# Top_Design.net
KiCad netlist of a schematic drawn in Altium Designer
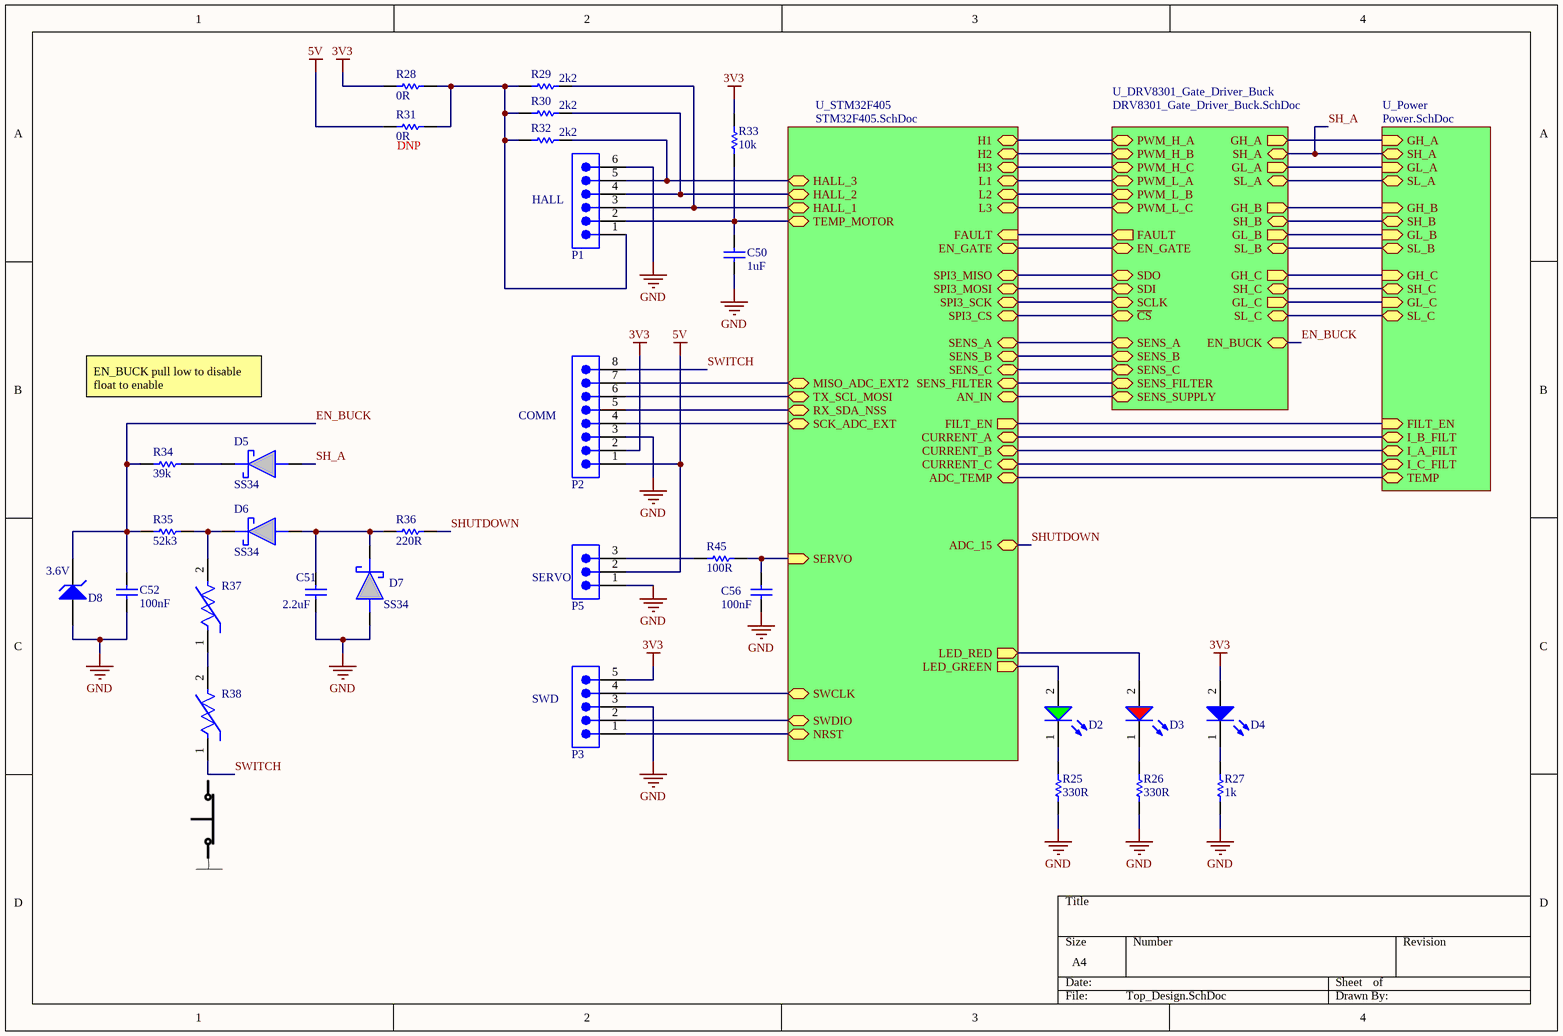
[diagram p0: Top_Design.SchDoc]

(export (version "E")
  (design (tool "Eeschema 10.0.6"))
  (components
    (comp (ref "C50")
      (value "1uF")
      (footprint "Wurth 0603 capacitor")
      (fields (field (name "Comment") "Generic Capacitor 1uF 0603"))
      (libsource (lib "Passives") (part "Generic Capacitor 1uF 0603"))
    )
    (comp (ref "C51")
      (value "2.2uF")
      (footprint "Wurth 0603 capacitor")
      (fields (field (name "Comment") "Generic Capacitor 2.2uF 0603"))
      (libsource (lib "Passives") (part "Generic Capacitor 2.2uF 0603"))
    )
    (comp (ref "C52")
      (value "100nF")
      (footprint "Wurth 0603 capacitor")
      (fields (field (name "Comment") "Generic Capacitor 100nF 0603"))
      (libsource (lib "Passives") (part "Generic Capacitor 100nF 0603"))
    )
    (comp (ref "C56")
      (value "100nF")
      (footprint "Wurth 0603 capacitor")
      (fields (field (name "Comment") "Generic Capacitor 100nF 0603"))
      (libsource (lib "Passives") (part "Generic Capacitor 100nF 0603"))
    )
    (comp (ref "D2")
      (value "Green, 3.2V, 140°")
      (footprint "Wurth 0603 LED")
      (description "WL-SMCD Mono-color Chip LED Diffused, SMT, size 0603, Green, 3.2V, 140°")
      (fields
        (field (name "MANUFACTURER PART NUMBER") "150060GS55040")
        (field (name "MANUFACTURER") "Wurth Elektronik")
      )
      (libsource (lib "LED") (part "LED GREEN 0603"))
    )
    (comp (ref "D3")
      (value "Red, 2V, 140°")
      (footprint "Wurth 0603 LED")
      (description "WL-SMCD Mono-color Chip LED Diffused, SMT, size 0603, Red, 2V, 140°")
      (fields
        (field (name "MANUFACTURER PART NUMBER") "150060RS55040")
        (field (name "MANUFACTURER") "Wurth Elektronik")
      )
      (libsource (lib "LED") (part "LED RED 0603"))
    )
    (comp (ref "D4")
      (value "Blue, 3.2V, 140°")
      (footprint "Wurth 0603 LED")
      (description "WL-SMCD Mono-color Chip LED Diffused, SMT, size 0603, Blue, 3.2V, 140°")
      (fields
        (field (name "MANUFACTURER PART NUMBER") "150060BS55040")
        (field (name "MANUFACTURER") "Wurth Elektronik")
      )
      (libsource (lib "LED") (part "LED BLUE 0603"))
    )
    (comp (ref "D5")
      (value "SS34")
      (footprint "MDD DO-214AC diode")
      (description "SS34 Schottky Barrier Diodes (SBD) SMA(DO-214AC) RoHS")
      (libsource (lib "Passives") (part "MDD SS34"))
    )
    (comp (ref "D6")
      (value "SS34")
      (footprint "MDD DO-214AC diode")
      (description "SS34 Schottky Barrier Diodes (SBD) SMA(DO-214AC) RoHS")
      (libsource (lib "Passives") (part "MDD SS34"))
    )
    (comp (ref "D7")
      (value "SS34")
      (footprint "MDD DO-214AC diode")
      (description "SS34 Schottky Barrier Diodes (SBD) SMA(DO-214AC) RoHS")
      (libsource (lib "Passives") (part "MDD SS34"))
    )
    (comp (ref "D8")
      (value "ROHM EDZVT2R3.6B")
      (footprint "ROHM SOD-523 zener")
      (description "Independent 3.6V~3.845V 150mW 3.6V SOD-523 Zener Diodes ROHS")
      (libsource (lib "Passives") (part "3.6V 150mW zener"))
    )
    (comp (ref "P1")
      (value "61300611121")
      (footprint "6x1 2.54mm M")
      (description "WR-PHD Pin Header, THT, Vertical, pitch 2.54mm, 1 Row, 6P")
      (fields (field (name "MANUFACTURER") "Wurth Elektronik"))
      (libsource (lib "2.54mm_pin_headers") (part "6P"))
    )
    (comp (ref "P2")
      (value "61300811121")
      (footprint "8x1 2.54mm M")
      (description "WR-PHD Pin Header, THT, Vertical, pitch 2.54mm, 1 Row, 8P")
      (fields (field (name "MANUFACTURER") "Wurth Elektronik"))
      (libsource (lib "2.54mm_pin_headers") (part "8P"))
    )
    (comp (ref "P3")
      (value "61300511121")
      (footprint "5x1 2.54mm M")
      (description "WR-PHD Pin Header, THT, Vertical, pitch 2.54mm, 1 Row, 5P")
      (fields (field (name "MANUFACTURER") "Wurth Elektronik"))
      (libsource (lib "2.54mm_pin_headers") (part "5P"))
    )
    (comp (ref "P5")
      (value "61300311121")
      (footprint "3x1 2.54mm M")
      (description "WR-PHD Pin Header, THT, Vertical, pitch 2.54mm, 1 Row, 3P")
      (fields (field (name "MANUFACTURER") "Wurth Elektronik"))
      (libsource (lib "2.54mm_pin_headers") (part "3P"))
    )
    (comp (ref "R25")
      (value "330R")
      (footprint "Wurth 0603 Resistor")
      (fields (field (name "Comment") "Generic Resistor 330R 0603"))
      (libsource (lib "Passives") (part "Generic Resistor 330R 0603"))
    )
    (comp (ref "R26")
      (value "330R")
      (footprint "Wurth 0603 Resistor")
      (fields (field (name "Comment") "Generic Resistor 330R 0603"))
      (libsource (lib "Passives") (part "Generic Resistor 330R 0603"))
    )
    (comp (ref "R27")
      (value "1k")
      (footprint "Wurth 0603 Resistor")
      (fields (field (name "Comment") "Generic Resistor 1k 0603"))
      (libsource (lib "Passives") (part "Generic Resistor 1k 0603"))
    )
    (comp (ref "R28")
      (value "0R")
      (footprint "Wurth 0603 Resistor")
      (fields (field (name "Comment") "Generic Resistor 0R 0603"))
      (libsource (lib "Passives") (part "Generic Resistor 0R 0603"))
    )
    (comp (ref "R29")
      (value "2k2")
      (footprint "Wurth 0603 Resistor")
      (fields (field (name "Comment") "Generic Resistor 2k2 0603"))
      (libsource (lib "Passives") (part "Generic Resistor 2k2 0603"))
    )
    (comp (ref "R30")
      (value "2k2")
      (footprint "Wurth 0603 Resistor")
      (fields (field (name "Comment") "Generic Resistor 2k2 0603"))
      (libsource (lib "Passives") (part "Generic Resistor 2k2 0603"))
    )
    (comp (ref "R31")
      (value "0R")
      (footprint "Wurth 0603 Resistor")
      (fields (field (name "Comment") "Generic Resistor 0R 0603"))
      (libsource (lib "Passives") (part "Generic Resistor 0R 0603"))
    )
    (comp (ref "R32")
      (value "2k2")
      (footprint "Wurth 0603 Resistor")
      (fields (field (name "Comment") "Generic Resistor 2k2 0603"))
      (libsource (lib "Passives") (part "Generic Resistor 2k2 0603"))
    )
    (comp (ref "R33")
      (value "10k")
      (footprint "Wurth 0603 Resistor")
      (fields (field (name "Comment") "Generic Resistor 10k 0603"))
      (libsource (lib "Passives") (part "Generic Resistor 10k 0603"))
    )
    (comp (ref "R34")
      (value "39k")
      (footprint "Wurth 0603 Resistor")
      (fields (field (name "Comment") "Generic Resistor 39k 0603"))
      (libsource (lib "Passives") (part "Generic Resistor 39k 0603"))
    )
    (comp (ref "R35")
      (value "52k3")
      (footprint "Wurth 0603 Resistor")
      (fields (field (name "Comment") "Generic Resistor 52k3 0603"))
      (libsource (lib "Passives") (part "Generic Resistor 52k3 0603"))
    )
    (comp (ref "R36")
      (value "220R")
      (footprint "Wurth 0603 Resistor")
      (fields (field (name "Comment") "Generic Resistor 220R 0603"))
      (libsource (lib "Passives") (part "Generic Resistor 220R 0603"))
    )
    (comp (ref "R37")
      (value "PRF15BC102RB6RC")
      (footprint "FP-PRF15-0_05-IPC_B")
      (description "THERMISTOR PTC 1K OHM 50% 0402")
      (fields (field (name "VOLTAGE") "32V") (field (name "TOLERANCE") "50%"))
      (libsource (lib "Altium Content Vault") (part "3b148a6ebabc5fb4d708a66c052d352"))
    )
    (comp (ref "R38")
      (value "PRF15BC102RB6RC")
      (footprint "FP-PRF15-0_05-IPC_B")
      (description "THERMISTOR PTC 1K OHM 50% 0402")
      (fields (field (name "VOLTAGE") "32V") (field (name "TOLERANCE") "50%"))
      (libsource (lib "Altium Content Vault") (part "3b148a6ebabc5fb4d708a66c052d352"))
    )
    (comp (ref "R45")
      (value "100R")
      (footprint "Wurth 0603 Resistor")
      (fields (field (name "Comment") "Generic Resistor 100R 0603"))
      (libsource (lib "Passives") (part "Generic Resistor 100R 0603"))
    )
  )
  (nets
    (net (code "6") (name "/EN_BUCK") (class "Default")
      (node (ref "C52") (pin "2") (pinfunction "2_2") (pintype "passive"))
      (node (ref "D8") (pin "1") (pinfunction "K_1") (pintype "passive"))
      (node (ref "R34") (pin "1") (pinfunction "1_1") (pintype "passive"))
      (node (ref "R35") (pin "1") (pinfunction "1_1") (pintype "passive"))
    )
    (net (code "19") (name "/HALL_1") (class "Default")
      (node (ref "P1") (pin "3") (pinfunction "3_3") (pintype "passive"))
      (node (ref "R29") (pin "2") (pinfunction "2_2") (pintype "passive"))
    )
    (net (code "20") (name "/HALL_2") (class "Default")
      (node (ref "P1") (pin "4") (pinfunction "4_4") (pintype "passive"))
      (node (ref "R30") (pin "2") (pinfunction "2_2") (pintype "passive"))
    )
    (net (code "21") (name "/HALL_3") (class "Default")
      (node (ref "P1") (pin "5") (pinfunction "5_5") (pintype "passive"))
      (node (ref "R32") (pin "2") (pinfunction "2_2") (pintype "passive"))
    )
    (net (code "25") (name "/LED_GREEN") (class "Default")
      (node (ref "D2") (pin "2") (pinfunction "A_2") (pintype "passive"))
    )
    (net (code "26") (name "/LED_RED") (class "Default")
      (node (ref "D3") (pin "2") (pinfunction "A_2") (pintype "passive"))
    )
    (net (code "27") (name "/MISO_ADC_EXT2") (class "Default")
      (node (ref "P2") (pin "7") (pinfunction "7_7") (pintype "passive"))
    )
    (net (code "28") (name "/NRST") (class "Default")
      (node (ref "P3") (pin "1") (pinfunction "1_1") (pintype "passive"))
    )
    (net (code "29") (name "/RX_SDA_NSS") (class "Default")
      (node (ref "P2") (pin "5") (pinfunction "5_5") (pintype "passive"))
    )
    (net (code "30") (name "/SCK_ADC_EXT") (class "Default")
      (node (ref "P2") (pin "4") (pinfunction "4_4") (pintype "passive"))
    )
    (net (code "38") (name "/SERVO") (class "Default")
      (node (ref "C56") (pin "2") (pinfunction "2_2") (pintype "passive"))
      (node (ref "R45") (pin "2") (pinfunction "2_2") (pintype "passive"))
    )
    (net (code "39") (name "/SHUTDOWN") (class "Default")
      (node (ref "R36") (pin "2") (pinfunction "2_2") (pintype "passive"))
    )
    (net (code "40") (name "/SH_A") (class "Default")
      (node (ref "D5") (pin "2") (pinfunction "A_2") (pintype "passive"))
    )
    (net (code "47") (name "/SWCLK") (class "Default")
      (node (ref "P3") (pin "4") (pinfunction "4_4") (pintype "passive"))
    )
    (net (code "48") (name "/SWDIO") (class "Default")
      (node (ref "P3") (pin "2") (pinfunction "2_2") (pintype "passive"))
    )
    (net (code "49") (name "/SWITCH") (class "Default")
      (node (ref "P2") (pin "8") (pinfunction "8_8") (pintype "passive"))
      (node (ref "R38") (pin "1") (pinfunction "1_1") (pintype "passive"))
    )
    (net (code "50") (name "/TEMP_MOTOR") (class "Default")
      (node (ref "C50") (pin "2") (pinfunction "2_2") (pintype "passive"))
      (node (ref "P1") (pin "2") (pinfunction "2_2") (pintype "passive"))
      (node (ref "R33") (pin "1") (pinfunction "1_1") (pintype "passive"))
    )
    (net (code "51") (name "/TX_SCL_MOSI") (class "Default")
      (node (ref "P2") (pin "6") (pinfunction "6_6") (pintype "passive"))
    )
    (net (code "52") (name "3V3") (class "Default")
      (node (ref "D4") (pin "2") (pinfunction "A_2") (pintype "passive"))
      (node (ref "P2") (pin "2") (pinfunction "2_2") (pintype "passive"))
      (node (ref "P3") (pin "5") (pinfunction "5_5") (pintype "passive"))
      (node (ref "R28") (pin "2") (pinfunction "2_2") (pintype "passive"))
      (node (ref "R33") (pin "2") (pinfunction "2_2") (pintype "passive"))
    )
    (net (code "53") (name "5V") (class "Default")
      (node (ref "P2") (pin "1") (pinfunction "1_1") (pintype "passive"))
      (node (ref "P5") (pin "2") (pinfunction "2_2") (pintype "passive"))
      (node (ref "R31") (pin "2") (pinfunction "2_2") (pintype "passive"))
    )
    (net (code "54") (name "GND") (class "Default")
      (node (ref "C50") (pin "1") (pinfunction "1_1") (pintype "passive"))
      (node (ref "C51") (pin "1") (pinfunction "1_1") (pintype "passive"))
      (node (ref "C52") (pin "1") (pinfunction "1_1") (pintype "passive"))
      (node (ref "C56") (pin "1") (pinfunction "1_1") (pintype "passive"))
      (node (ref "D7") (pin "2") (pinfunction "A_2") (pintype "passive"))
      (node (ref "D8") (pin "2") (pinfunction "A_2") (pintype "passive"))
      (node (ref "P1") (pin "6") (pinfunction "6_6") (pintype "passive"))
      (node (ref "P2") (pin "3") (pinfunction "3_3") (pintype "passive"))
      (node (ref "P3") (pin "3") (pinfunction "3_3") (pintype "passive"))
      (node (ref "P5") (pin "1") (pinfunction "1_1") (pintype "passive"))
      (node (ref "R25") (pin "2") (pinfunction "2_2") (pintype "passive"))
      (node (ref "R26") (pin "2") (pinfunction "2_2") (pintype "passive"))
      (node (ref "R27") (pin "2") (pinfunction "2_2") (pintype "passive"))
    )
    (net (code "55") (name "Net-(D2-K)") (class "Default")
      (node (ref "D2") (pin "1") (pinfunction "K_1") (pintype "passive"))
      (node (ref "R25") (pin "1") (pinfunction "1_1") (pintype "passive"))
    )
    (net (code "56") (name "Net-(D3-K)") (class "Default")
      (node (ref "D3") (pin "1") (pinfunction "K_1") (pintype "passive"))
      (node (ref "R26") (pin "1") (pinfunction "1_1") (pintype "passive"))
    )
    (net (code "57") (name "Net-(D4-K)") (class "Default")
      (node (ref "D4") (pin "1") (pinfunction "K_1") (pintype "passive"))
      (node (ref "R27") (pin "1") (pinfunction "1_1") (pintype "passive"))
    )
    (net (code "58") (name "Net-(D5-K)") (class "Default")
      (node (ref "D5") (pin "1") (pinfunction "K_1") (pintype "passive"))
      (node (ref "R34") (pin "2") (pinfunction "2_2") (pintype "passive"))
    )
    (net (code "59") (name "Net-(D6-A)") (class "Default")
      (node (ref "C51") (pin "2") (pinfunction "2_2") (pintype "passive"))
      (node (ref "D6") (pin "2") (pinfunction "A_2") (pintype "passive"))
      (node (ref "D7") (pin "1") (pinfunction "K_1") (pintype "passive"))
      (node (ref "R36") (pin "1") (pinfunction "1_1") (pintype "passive"))
    )
    (net (code "60") (name "Net-(D6-K)") (class "Default")
      (node (ref "D6") (pin "1") (pinfunction "K_1") (pintype "passive"))
      (node (ref "R35") (pin "2") (pinfunction "2_2") (pintype "passive"))
      (node (ref "R37") (pin "2") (pinfunction "2_2") (pintype "passive"))
    )
    (net (code "61") (name "Net-(P1-Pad1)") (class "Default")
      (node (ref "P1") (pin "1") (pinfunction "1_1") (pintype "passive"))
      (node (ref "R28") (pin "1") (pinfunction "1_1") (pintype "passive"))
      (node (ref "R29") (pin "1") (pinfunction "1_1") (pintype "passive"))
      (node (ref "R30") (pin "1") (pinfunction "1_1") (pintype "passive"))
      (node (ref "R31") (pin "1") (pinfunction "1_1") (pintype "passive"))
      (node (ref "R32") (pin "1") (pinfunction "1_1") (pintype "passive"))
    )
    (net (code "62") (name "Net-(P5-Pad3)") (class "Default")
      (node (ref "P5") (pin "3") (pinfunction "3_3") (pintype "passive"))
      (node (ref "R45") (pin "1") (pinfunction "1_1") (pintype "passive"))
    )
    (net (code "63") (name "Net-(R37-Pad1)") (class "Default")
      (node (ref "R37") (pin "1") (pinfunction "1_1") (pintype "passive"))
      (node (ref "R38") (pin "2") (pinfunction "2_2") (pintype "passive"))
    )
  )
)
